# Schematic_v78.net
KiCad netlist of a schematic drawn in EAGLE
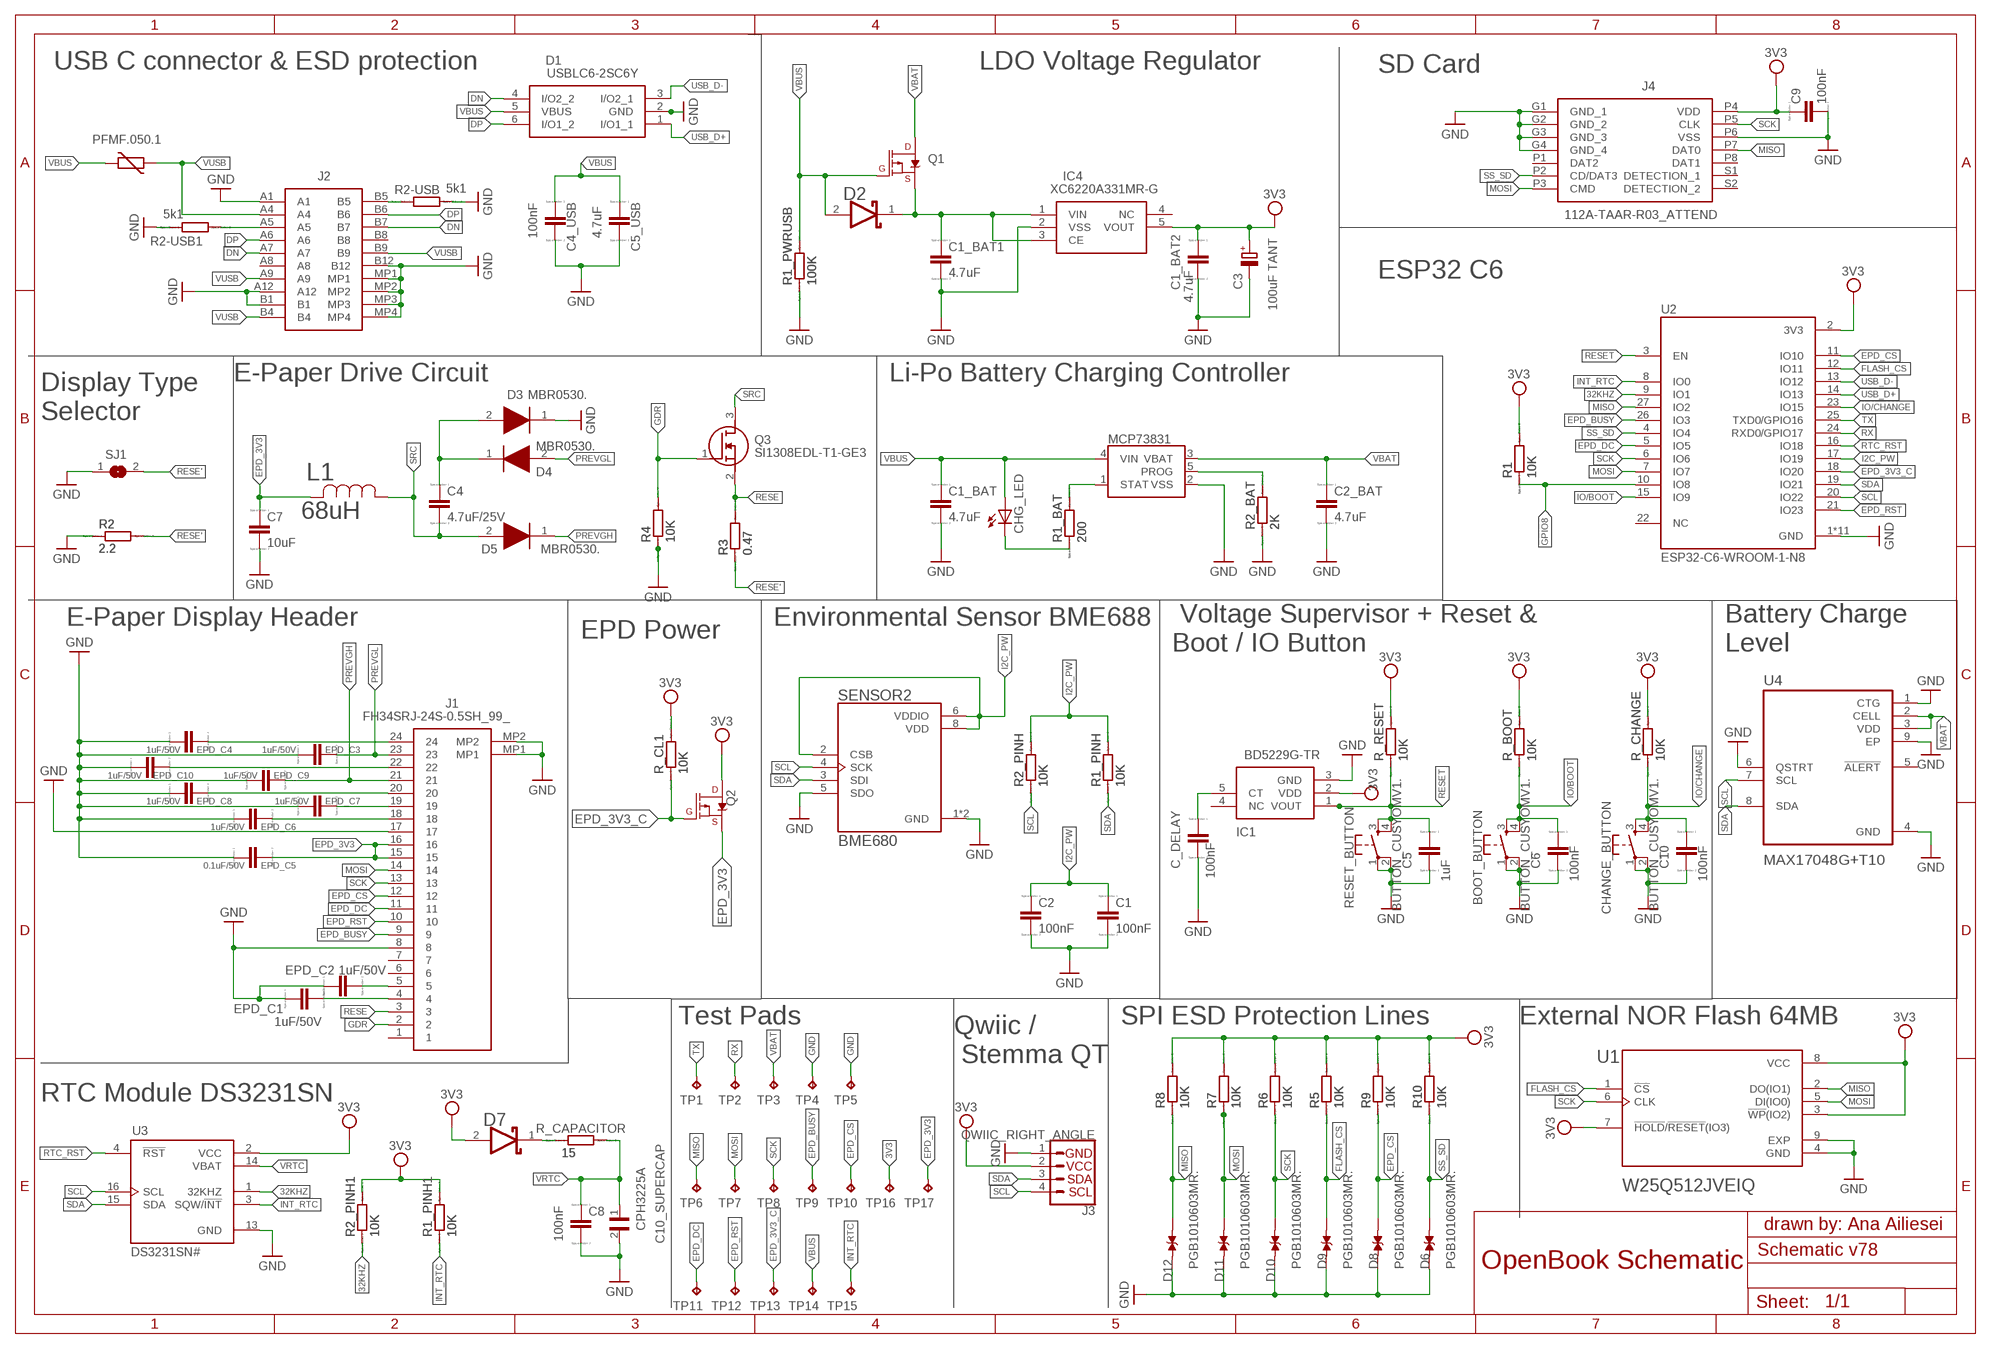
[diagram p0: schematic, sheet 1]

(export (version "E")
  (design (tool "Eeschema 10.0.6"))
  (components
    (comp (ref "BOOT_BUTTON")
      (value "BUTTON_CUSYOMV1.")
      (footprint "eagle-import:MYBUTTON")
      (libsource (lib "eagle-import") (part "BUTTON_CUSYOMV1."))
    )
    (comp (ref "C1")
      (value "100nF")
      (footprint "eagle-import:EAGLE-LTSPICE_C0402")
      (libsource (lib "eagle-import") (part "EAGLE-LTSPICE_C"))
    )
    (comp (ref "C1_BAT")
      (value "4.7uF")
      (footprint "eagle-import:EAGLE-LTSPICE_C0402")
      (libsource (lib "eagle-import") (part "EAGLE-LTSPICE_C"))
    )
    (comp (ref "C1_BAT1")
      (value "4.7uF")
      (footprint "eagle-import:EAGLE-LTSPICE_C0402")
      (libsource (lib "eagle-import") (part "EAGLE-LTSPICE_C"))
    )
    (comp (ref "C1_BAT2")
      (value "4.7uF")
      (footprint "eagle-import:EAGLE-LTSPICE_C0402")
      (libsource (lib "eagle-import") (part "EAGLE-LTSPICE_C"))
    )
    (comp (ref "C2")
      (value "100nF")
      (footprint "eagle-import:EAGLE-LTSPICE_C0402")
      (libsource (lib "eagle-import") (part "EAGLE-LTSPICE_C"))
    )
    (comp (ref "C2_BAT")
      (value "4.7uF")
      (footprint "eagle-import:EAGLE-LTSPICE_C0402")
      (libsource (lib "eagle-import") (part "EAGLE-LTSPICE_C"))
    )
    (comp (ref "C3")
      (value "100uF TANT")
      (footprint "eagle-import:RCL_CT3528")
      (libsource (lib "eagle-import") (part "RCL_CPOL-EUCT3528"))
    )
    (comp (ref "C4")
      (value "4.7uF/25V")
      (footprint "eagle-import:EAGLE-LTSPICE_C0402")
      (libsource (lib "eagle-import") (part "EAGLE-LTSPICE_C"))
    )
    (comp (ref "C4_USB")
      (value "100nF")
      (footprint "eagle-import:EAGLE-LTSPICE_C0402")
      (libsource (lib "eagle-import") (part "EAGLE-LTSPICE_C"))
    )
    (comp (ref "C5")
      (value "1uF")
      (footprint "eagle-import:EAGLE-LTSPICE_C0402")
      (libsource (lib "eagle-import") (part "EAGLE-LTSPICE_C"))
    )
    (comp (ref "C5_USB")
      (value "4.7uF")
      (footprint "eagle-import:EAGLE-LTSPICE_C0402")
      (libsource (lib "eagle-import") (part "EAGLE-LTSPICE_C"))
    )
    (comp (ref "C6")
      (value "100nF")
      (footprint "eagle-import:EAGLE-LTSPICE_C0402")
      (libsource (lib "eagle-import") (part "EAGLE-LTSPICE_C"))
    )
    (comp (ref "C7")
      (value "10uF")
      (footprint "eagle-import:EAGLE-LTSPICE_C0402")
      (libsource (lib "eagle-import") (part "EAGLE-LTSPICE_C"))
    )
    (comp (ref "C8")
      (value "100nF")
      (footprint "eagle-import:EAGLE-LTSPICE_C0402")
      (libsource (lib "eagle-import") (part "EAGLE-LTSPICE_C"))
    )
    (comp (ref "C9")
      (value "100nF")
      (footprint "eagle-import:EAGLE-LTSPICE_C0402")
      (libsource (lib "eagle-import") (part "EAGLE-LTSPICE_C"))
    )
    (comp (ref "C10")
      (value "100nF")
      (footprint "eagle-import:EAGLE-LTSPICE_C0402")
      (libsource (lib "eagle-import") (part "EAGLE-LTSPICE_C"))
    )
    (comp (ref "C10_SUPERCAP")
      (value "CPH3225A")
      (footprint "eagle-import:CAPCP3225X100N")
      (fields (field (name "MF") "Seiko Instruments"))
      (libsource (lib "eagle-import") (part "CPH3225A"))
    )
    (comp (ref "CHANGE_BUTTON")
      (value "BUTTON_CUSYOMV1.")
      (footprint "eagle-import:MYBUTTON")
      (libsource (lib "eagle-import") (part "BUTTON_CUSYOMV1."))
    )
    (comp (ref "CHG_LED")
      (value "ADAFRUIT_LEDCHIP-LED0603")
      (footprint "eagle-import:ADAFRUIT_CHIP-LED0603")
      (libsource (lib "eagle-import") (part "ADAFRUIT_LEDCHIP-LED0603"))
    )
    (comp (ref "C_DELAY")
      (value "100nF")
      (footprint "eagle-import:EAGLE-LTSPICE_C0402")
      (libsource (lib "eagle-import") (part "EAGLE-LTSPICE_C"))
    )
    (comp (ref "D1")
      (value "USBLC6-2SC6Y")
      (footprint "eagle-import:SOT95P280X145-6N")
      (fields (field (name "MF") "STMicroelectronics"))
      (libsource (lib "eagle-import") (part "USBLC6-2SC6Y"))
    )
    (comp (ref "D2")
      (value "ESP32_WROVER_AVX---SD0805S020S1R0_AVX_SD0805S020S1R0_0_0")
      (footprint "eagle-import:ESP32_WROVER_AVX---SD0805S020S1R0_AVX_SD0805S020S1R0_0")
      (libsource (lib "eagle-import") (part "ESP32_WROVER_AVX---SD0805S020S1R0_AVX_SD0805S020S1R0_0_0"))
    )
    (comp (ref "D3")
      (value "MBR0530.")
      (footprint "eagle-import:SOD3716X135N")
      (libsource (lib "eagle-import") (part "MBR0530."))
    )
    (comp (ref "D4")
      (value "MBR0530.")
      (footprint "eagle-import:SOD3716X135N")
      (libsource (lib "eagle-import") (part "MBR0530."))
    )
    (comp (ref "D5")
      (value "MBR0530.")
      (footprint "eagle-import:SOD3716X135N")
      (libsource (lib "eagle-import") (part "MBR0530."))
    )
    (comp (ref "D6")
      (value "PGB1010603MR.")
      (footprint "eagle-import:DIOC1608X36N")
      (libsource (lib "eagle-import") (part "PGB1010603MR."))
    )
    (comp (ref "D7")
      (value "SD0805S020S1R0")
      (footprint "eagle-import:ESP32_WROVER_AVX---SD0805S020S1R0_AVX_SD0805S020S1R0_0")
      (libsource (lib "eagle-import") (part "ESP32_WROVER_AVX---SD0805S020S1R0_AVX_SD0805S020S1R0_0_0"))
    )
    (comp (ref "D8")
      (value "PGB1010603MR.")
      (footprint "eagle-import:DIOC1608X36N")
      (libsource (lib "eagle-import") (part "PGB1010603MR."))
    )
    (comp (ref "D9")
      (value "PGB1010603MR.")
      (footprint "eagle-import:DIOC1608X36N")
      (libsource (lib "eagle-import") (part "PGB1010603MR."))
    )
    (comp (ref "D10")
      (value "PGB1010603MR.")
      (footprint "eagle-import:DIOC1608X36N")
      (libsource (lib "eagle-import") (part "PGB1010603MR."))
    )
    (comp (ref "D11")
      (value "PGB1010603MR.")
      (footprint "eagle-import:DIOC1608X36N")
      (libsource (lib "eagle-import") (part "PGB1010603MR."))
    )
    (comp (ref "D12")
      (value "PGB1010603MR.")
      (footprint "eagle-import:DIOC1608X36N")
      (libsource (lib "eagle-import") (part "PGB1010603MR."))
    )
    (comp (ref "EPD_C1")
      (value "1uF/50V")
      (footprint "eagle-import:EAGLE-LTSPICE_C0402")
      (libsource (lib "eagle-import") (part "EAGLE-LTSPICE_C"))
    )
    (comp (ref "EPD_C2")
      (value "1uF/50V")
      (footprint "eagle-import:EAGLE-LTSPICE_C0402")
      (libsource (lib "eagle-import") (part "EAGLE-LTSPICE_C"))
    )
    (comp (ref "EPD_C3")
      (value "1uF/50V")
      (footprint "eagle-import:EAGLE-LTSPICE_C0402")
      (libsource (lib "eagle-import") (part "EAGLE-LTSPICE_C"))
    )
    (comp (ref "EPD_C4")
      (value "1uF/50V")
      (footprint "eagle-import:EAGLE-LTSPICE_C0402")
      (libsource (lib "eagle-import") (part "EAGLE-LTSPICE_C"))
    )
    (comp (ref "EPD_C5")
      (value "0.1uF/50V")
      (footprint "eagle-import:EAGLE-LTSPICE_C0402")
      (libsource (lib "eagle-import") (part "EAGLE-LTSPICE_C"))
    )
    (comp (ref "EPD_C6")
      (value "1uF/50V")
      (footprint "eagle-import:EAGLE-LTSPICE_C0402")
      (libsource (lib "eagle-import") (part "EAGLE-LTSPICE_C"))
    )
    (comp (ref "EPD_C7")
      (value "1uF/50V")
      (footprint "eagle-import:EAGLE-LTSPICE_C0402")
      (libsource (lib "eagle-import") (part "EAGLE-LTSPICE_C"))
    )
    (comp (ref "EPD_C8")
      (value "1uF/50V")
      (footprint "eagle-import:EAGLE-LTSPICE_C0402")
      (libsource (lib "eagle-import") (part "EAGLE-LTSPICE_C"))
    )
    (comp (ref "EPD_C9")
      (value "1uF/50V")
      (footprint "eagle-import:EAGLE-LTSPICE_C0402")
      (libsource (lib "eagle-import") (part "EAGLE-LTSPICE_C"))
    )
    (comp (ref "EPD_C10")
      (value "1uF/50V")
      (footprint "eagle-import:EAGLE-LTSPICE_C0402")
      (libsource (lib "eagle-import") (part "EAGLE-LTSPICE_C"))
    )
    (comp (ref "IC1")
      (value "BD5229G-TR")
      (footprint "eagle-import:SOT95P280X125-5N")
      (fields (field (name "MOUSER_PART_NUMBER") "755-BD5229G-TR"))
      (libsource (lib "eagle-import") (part "BD5229G-TR"))
    )
    (comp (ref "IC4")
      (value "XC6220A331MR-G")
      (footprint "eagle-import:SOT95P280X120-5N")
      (fields (field (name "MOUSER_PART_NUMBER") "865-XC6220A331MR-G"))
      (libsource (lib "eagle-import") (part "XC6220A331MR-G"))
    )
    (comp (ref "J1")
      (value "FH34SRJ-24S-0.5SH_99_")
      (footprint "eagle-import:FH34SRJ24S05SH99")
      (fields
        (field (name "MANUFACTURER_PART_NUMBER") "FH34SRJ-24S-0.5SH(99)")
        (field (name "MOUSER_PART_NUMBER") "798-FH34SRJ24S05SH99")
      )
      (libsource (lib "eagle-import") (part "FH34SRJ-24S-0.5SH_99_"))
    )
    (comp (ref "J2")
      (value "SAMACSYS_PARTS_USB4110-GF-A")
      (footprint "eagle-import:SAMACSYS_PARTS_USB4110GFA")
      (fields
        (field (name "MANUFACTURER_PART_NUMBER") "USB4110-GF-A")
        (field (name "MOUSER_PART_NUMBER") "640-USB4110-GF-A")
      )
      (libsource (lib "eagle-import") (part "SAMACSYS_PARTS_USB4110-GF-A"))
    )
    (comp (ref "J3")
      (value "QWIIC_RIGHT_ANGLE")
      (footprint "eagle-import:JST04_1MM_RA")
      (libsource (lib "eagle-import") (part "QWIIC_CONNECTORJS-1MM"))
    )
    (comp (ref "J4")
      (value "112A-TAAR-R03_ATTEND")
      (footprint "eagle-import:112ATAARR03ATTEND")
      (fields (field (name "MANUFACTURER_PART_NUMBER") "112A-TAAR-R03 ATTEND"))
      (libsource (lib "eagle-import") (part "112A-TAAR-R03_ATTEND"))
    )
    (comp (ref "L1")
      (value "68uH")
      (footprint "eagle-import:IND_4828-WE-TPC_WRE")
      (fields
        (field (name "MANUFACTURER_PART_NUMBER") "744043680")
        (field (name "COPYRIGHT") "Copyright (C) 2024 Ultra Librarian. All rights reserved.")
      )
      (libsource (lib "eagle-import") (part "744043680IND_4828-WE-TPC_WRE"))
    )
    (comp (ref "MCP73831")
      (value "ESP32_WROVER_SPARKFUN-IC-POWER_MCP73831")
      (footprint "eagle-import:ESP32_WROVER_SPARKFUN-IC-POWER_SOT23-5")
      (libsource (lib "eagle-import") (part "ESP32_WROVER_SPARKFUN-IC-POWER_MCP73831"))
    )
    (comp (ref "PFMF.050.1")
      (value "ESP32C6_VARISTORCN1812")
      (footprint "eagle-import:ESP32C6_VARISTOR_CT_CN1812")
      (libsource (lib "eagle-import") (part "ESP32C6_VARISTORCN1812"))
    )
    (comp (ref "Q1")
      (value "20V/4.2A/52mΩ/1.4W")
      (footprint "eagle-import:ESP32_WROVER_SPARKFUN-DISCRETESEMI_SOT23-3")
      (libsource (lib "eagle-import") (part "ESP32_WROVER_SPARKFUN-DISCRETESEMI_MOSFET_PCH"))
    )
    (comp (ref "Q2")
      (value "20V/4.2A/52mΩ/1.4W")
      (footprint "eagle-import:ESP32_WROVER_SPARKFUN-DISCRETESEMI_SOT23-3")
      (libsource (lib "eagle-import") (part "ESP32_WROVER_SPARKFUN-DISCRETESEMI_MOSFET_PCH"))
    )
    (comp (ref "Q3")
      (value "SI1308EDL-T1-GE3")
      (footprint "eagle-import:SOT65P210X110-3N")
      (fields (field (name "MF") "Vishay Siliconix"))
      (libsource (lib "eagle-import") (part "SI1308EDL-T1-GE3"))
    )
    (comp (ref "R1")
      (value "10K")
      (footprint "eagle-import:ESP32_WROVER_EAGLE-LTSPICE_R0402")
      (libsource (lib "eagle-import") (part "ESP32_WROVER_EAGLE-LTSPICE_R"))
    )
    (comp (ref "R1_BAT")
      (value "200")
      (footprint "eagle-import:ESP32_WROVER_EAGLE-LTSPICE_R0402")
      (libsource (lib "eagle-import") (part "ESP32_WROVER_EAGLE-LTSPICE_R"))
    )
    (comp (ref "R1_PINH")
      (value "10K")
      (footprint "eagle-import:ESP32_WROVER_EAGLE-LTSPICE_R0402")
      (libsource (lib "eagle-import") (part "ESP32_WROVER_EAGLE-LTSPICE_R"))
    )
    (comp (ref "R1_PINH1")
      (value "10K")
      (footprint "eagle-import:ESP32_WROVER_EAGLE-LTSPICE_R0402")
      (libsource (lib "eagle-import") (part "ESP32_WROVER_EAGLE-LTSPICE_R"))
    )
    (comp (ref "R1_PWRUSB")
      (value "100K")
      (footprint "eagle-import:ESP32_WROVER_EAGLE-LTSPICE_R0402")
      (libsource (lib "eagle-import") (part "ESP32_WROVER_EAGLE-LTSPICE_R"))
    )
    (comp (ref "R2")
      (value "2.2")
      (footprint "eagle-import:ESP32_WROVER_EAGLE-LTSPICE_R0402")
      (libsource (lib "eagle-import") (part "ESP32_WROVER_EAGLE-LTSPICE_R"))
    )
    (comp (ref "R2-USB")
      (value "5k1")
      (footprint "eagle-import:ESP32_WROVER_EAGLE-LTSPICE_R0402")
      (libsource (lib "eagle-import") (part "ESP32_WROVER_EAGLE-LTSPICE_R"))
    )
    (comp (ref "R2-USB1")
      (value "5k1")
      (footprint "eagle-import:ESP32_WROVER_EAGLE-LTSPICE_R0402")
      (libsource (lib "eagle-import") (part "ESP32_WROVER_EAGLE-LTSPICE_R"))
    )
    (comp (ref "R2_BAT")
      (value "2K")
      (footprint "eagle-import:ESP32_WROVER_EAGLE-LTSPICE_R0402")
      (libsource (lib "eagle-import") (part "ESP32_WROVER_EAGLE-LTSPICE_R"))
    )
    (comp (ref "R2_PINH")
      (value "10K")
      (footprint "eagle-import:ESP32_WROVER_EAGLE-LTSPICE_R0402")
      (libsource (lib "eagle-import") (part "ESP32_WROVER_EAGLE-LTSPICE_R"))
    )
    (comp (ref "R2_PINH1")
      (value "10K")
      (footprint "eagle-import:ESP32_WROVER_EAGLE-LTSPICE_R0402")
      (libsource (lib "eagle-import") (part "ESP32_WROVER_EAGLE-LTSPICE_R"))
    )
    (comp (ref "R3")
      (value "0.47")
      (footprint "eagle-import:ESP32_WROVER_EAGLE-LTSPICE_R0402")
      (libsource (lib "eagle-import") (part "ESP32_WROVER_EAGLE-LTSPICE_R"))
    )
    (comp (ref "R4")
      (value "10K")
      (footprint "eagle-import:ESP32_WROVER_EAGLE-LTSPICE_R0402")
      (libsource (lib "eagle-import") (part "ESP32_WROVER_EAGLE-LTSPICE_R"))
    )
    (comp (ref "R5")
      (value "10K")
      (footprint "eagle-import:ESP32_WROVER_EAGLE-LTSPICE_R0402")
      (libsource (lib "eagle-import") (part "ESP32_WROVER_EAGLE-LTSPICE_R"))
    )
    (comp (ref "R6")
      (value "10K")
      (footprint "eagle-import:ESP32_WROVER_EAGLE-LTSPICE_R0402")
      (libsource (lib "eagle-import") (part "ESP32_WROVER_EAGLE-LTSPICE_R"))
    )
    (comp (ref "R7")
      (value "10K")
      (footprint "eagle-import:ESP32_WROVER_EAGLE-LTSPICE_R0402")
      (libsource (lib "eagle-import") (part "ESP32_WROVER_EAGLE-LTSPICE_R"))
    )
    (comp (ref "R8")
      (value "10K")
      (footprint "eagle-import:ESP32_WROVER_EAGLE-LTSPICE_R0402")
      (libsource (lib "eagle-import") (part "ESP32_WROVER_EAGLE-LTSPICE_R"))
    )
    (comp (ref "R9")
      (value "10K")
      (footprint "eagle-import:ESP32_WROVER_EAGLE-LTSPICE_R0402")
      (libsource (lib "eagle-import") (part "ESP32_WROVER_EAGLE-LTSPICE_R"))
    )
    (comp (ref "R10")
      (value "10K")
      (footprint "eagle-import:ESP32_WROVER_EAGLE-LTSPICE_R0402")
      (libsource (lib "eagle-import") (part "ESP32_WROVER_EAGLE-LTSPICE_R"))
    )
    (comp (ref "RESET_BUTTON")
      (value "BUTTON_CUSYOMV1.")
      (footprint "eagle-import:MYBUTTON")
      (libsource (lib "eagle-import") (part "BUTTON_CUSYOMV1."))
    )
    (comp (ref "R_BOOT")
      (value "10K")
      (footprint "eagle-import:ESP32_WROVER_EAGLE-LTSPICE_R0402")
      (libsource (lib "eagle-import") (part "ESP32_WROVER_EAGLE-LTSPICE_R"))
    )
    (comp (ref "R_CAPACITOR")
      (value "15")
      (footprint "eagle-import:ESP32_WROVER_EAGLE-LTSPICE_R0402")
      (libsource (lib "eagle-import") (part "ESP32_WROVER_EAGLE-LTSPICE_R"))
    )
    (comp (ref "R_CHANGE")
      (value "10K")
      (footprint "eagle-import:ESP32_WROVER_EAGLE-LTSPICE_R0402")
      (libsource (lib "eagle-import") (part "ESP32_WROVER_EAGLE-LTSPICE_R"))
    )
    (comp (ref "R_CL1")
      (value "10K")
      (footprint "eagle-import:ESP32_WROVER_EAGLE-LTSPICE_R0402")
      (libsource (lib "eagle-import") (part "ESP32_WROVER_EAGLE-LTSPICE_R"))
    )
    (comp (ref "R_RESET")
      (value "10K")
      (footprint "eagle-import:ESP32_WROVER_EAGLE-LTSPICE_R0402")
      (libsource (lib "eagle-import") (part "ESP32_WROVER_EAGLE-LTSPICE_R"))
    )
    (comp (ref "SENSOR2")
      (value "BME680")
      (footprint "eagle-import:ESP32_WROVER_BME680_PSON80P300X300X100-8N")
      (fields (field (name "MF") "Bosch Sensortec"))
      (libsource (lib "eagle-import") (part "ESP32_WROVER_BME680_BME680"))
    )
    (comp (ref "SJ1") (value "SJ") (footprint "eagle-import:SJ") (libsource (lib "eagle-import") (part "SJ")))
    (comp (ref "TP1")
      (value "TX")
      (footprint "eagle-import:TP20R")
      (libsource (lib "eagle-import") (part "TP"))
    )
    (comp (ref "TP2")
      (value "RX")
      (footprint "eagle-import:TP20R")
      (libsource (lib "eagle-import") (part "TP"))
    )
    (comp (ref "TP3")
      (value "VBAT")
      (footprint "eagle-import:TP20R")
      (libsource (lib "eagle-import") (part "TP"))
    )
    (comp (ref "TP4")
      (value "GND")
      (footprint "eagle-import:TP20R")
      (libsource (lib "eagle-import") (part "TP"))
    )
    (comp (ref "TP5")
      (value "GND")
      (footprint "eagle-import:TP20R")
      (libsource (lib "eagle-import") (part "TP"))
    )
    (comp (ref "TP6")
      (value "MISO")
      (footprint "eagle-import:TP20R")
      (libsource (lib "eagle-import") (part "TP"))
    )
    (comp (ref "TP7")
      (value "MOSI")
      (footprint "eagle-import:TP20R")
      (libsource (lib "eagle-import") (part "TP"))
    )
    (comp (ref "TP8")
      (value "SCK")
      (footprint "eagle-import:TP20R")
      (libsource (lib "eagle-import") (part "TP"))
    )
    (comp (ref "TP9")
      (value "EPD_BUSY")
      (footprint "eagle-import:TP20R")
      (libsource (lib "eagle-import") (part "TP"))
    )
    (comp (ref "TP10")
      (value "EPD_CS")
      (footprint "eagle-import:TP20R")
      (libsource (lib "eagle-import") (part "TP"))
    )
    (comp (ref "TP11")
      (value "EPD_DC")
      (footprint "eagle-import:TP20R")
      (libsource (lib "eagle-import") (part "TP"))
    )
    (comp (ref "TP12")
      (value "EPD_RST")
      (footprint "eagle-import:TP20R")
      (libsource (lib "eagle-import") (part "TP"))
    )
    (comp (ref "TP13")
      (value "EPD_3V3_C")
      (footprint "eagle-import:TP20R")
      (libsource (lib "eagle-import") (part "TP"))
    )
    (comp (ref "TP14")
      (value "VBUS")
      (footprint "eagle-import:TP20R")
      (libsource (lib "eagle-import") (part "TP"))
    )
    (comp (ref "TP15")
      (value "INT_RTC")
      (footprint "eagle-import:TP20R")
      (libsource (lib "eagle-import") (part "TP"))
    )
    (comp (ref "TP16")
      (value "3V3")
      (footprint "eagle-import:TP20R")
      (libsource (lib "eagle-import") (part "TP"))
    )
    (comp (ref "TP17")
      (value "EPD_3V3")
      (footprint "eagle-import:TP20R")
      (libsource (lib "eagle-import") (part "TP"))
    )
    (comp (ref "U1")
      (value "W25Q512JVEIQ")
      (footprint "eagle-import:SON127P600X800X80-9N")
      (fields (field (name "MF") "Winbond Electronics"))
      (libsource (lib "eagle-import") (part "W25Q512JVEIQ"))
    )
    (comp (ref "U2")
      (value "ESP32-C6-WROOM-1-N8")
      (footprint "eagle-import:XCVR_ESP32-C6-WROOM-1-N8")
      (fields (field (name "MF") "Espressif Systems"))
      (libsource (lib "eagle-import") (part "ESP32-C6-WROOM-1-N8"))
    )
    (comp (ref "U3")
      (value "DS3231SN#")
      (footprint "eagle-import:SOIC127P1032X265-16N")
      (fields (field (name "MF") "Analog Devices"))
      (libsource (lib "eagle-import") (part "DS3231SN#"))
    )
    (comp (ref "U4")
      (value "MAX17048G+T10")
      (footprint "eagle-import:SON50P200X200X80-9N")
      (fields (field (name "MF") "Analog Devices"))
      (libsource (lib "eagle-import") (part "MAX17048G+T10"))
    )
  )
  (nets
    (net (code "1") (name "3V3") (class "Default")
      (node (ref "C1_BAT2") (pin "1") (pinfunction "1_1") (pintype "passive"))
      (node (ref "C3") (pin "+") (pinfunction "+_+") (pintype "passive"))
      (node (ref "C9") (pin "1") (pinfunction "1_1") (pintype "passive"))
      (node (ref "D7") (pin "2") (pinfunction "ANODE_2") (pintype "bidirectional"))
      (node (ref "IC1") (pin "2") (pinfunction "VDD_2") (pintype "bidirectional"))
      (node (ref "IC4") (pin "5") (pinfunction "VOUT_5") (pintype "bidirectional"))
      (node (ref "J3") (pin "2") (pinfunction "2_2") (pintype "power_in"))
      (node (ref "J4") (pin "P4") (pinfunction "VDD_P4") (pintype "bidirectional"))
      (node (ref "Q2") (pin "3") (pinfunction "D_3") (pintype "bidirectional"))
      (node (ref "R1") (pin "2") (pinfunction "2_2") (pintype "passive"))
      (node (ref "R10") (pin "2") (pinfunction "2_2") (pintype "passive"))
      (node (ref "R1_PINH1") (pin "2") (pinfunction "2_2") (pintype "passive"))
      (node (ref "R2_PINH1") (pin "2") (pinfunction "2_2") (pintype "passive"))
      (node (ref "R5") (pin "2") (pinfunction "2_2") (pintype "passive"))
      (node (ref "R6") (pin "2") (pinfunction "2_2") (pintype "passive"))
      (node (ref "R7") (pin "2") (pinfunction "2_2") (pintype "passive"))
      (node (ref "R8") (pin "2") (pinfunction "2_2") (pintype "passive"))
      (node (ref "R9") (pin "2") (pinfunction "2_2") (pintype "passive"))
      (node (ref "R_BOOT") (pin "2") (pinfunction "2_2") (pintype "passive"))
      (node (ref "R_CHANGE") (pin "2") (pinfunction "2_2") (pintype "passive"))
      (node (ref "R_CL1") (pin "2") (pinfunction "2_2") (pintype "passive"))
      (node (ref "R_RESET") (pin "2") (pinfunction "2_2") (pintype "passive"))
      (node (ref "TP16") (pin "TP") (pinfunction "TP_TP") (pintype "input"))
      (node (ref "U1") (pin "3") (pinfunction "~{WP}(IO2)_3") (pintype "bidirectional"))
      (node (ref "U1") (pin "7") (pinfunction "~{HOLD}/~{RESET}(IO3)_7") (pintype "bidirectional"))
      (node (ref "U1") (pin "8") (pinfunction "VCC_8") (pintype "power_in"))
      (node (ref "U2") (pin "2") (pinfunction "3V3_2") (pintype "power_in"))
      (node (ref "U3") (pin "2") (pinfunction "VCC_2") (pintype "power_in"))
    )
    (net (code "2") (name "32KHZ") (class "Default")
      (node (ref "R2_PINH1") (pin "1") (pinfunction "1_1") (pintype "passive"))
      (node (ref "U2") (pin "9") (pinfunction "IO1_9") (pintype "bidirectional"))
      (node (ref "U3") (pin "1") (pinfunction "32KHZ_1") (pintype "output"))
    )
    (net (code "3") (name "DN") (class "Default")
      (node (ref "D1") (pin "4") (pinfunction "I/O2_2_4") (pintype "bidirectional"))
      (node (ref "J2") (pin "A7") (pinfunction "A7_A7") (pintype "bidirectional"))
      (node (ref "J2") (pin "B7") (pinfunction "B7_B7") (pintype "bidirectional"))
    )
    (net (code "4") (name "DP") (class "Default")
      (node (ref "D1") (pin "6") (pinfunction "I/O1_2_6") (pintype "bidirectional"))
      (node (ref "J2") (pin "A6") (pinfunction "A6_A6") (pintype "bidirectional"))
      (node (ref "J2") (pin "B6") (pinfunction "B6_B6") (pintype "bidirectional"))
    )
    (net (code "5") (name "EPD_3V3") (class "Default")
      (node (ref "C7") (pin "1") (pinfunction "1_1") (pintype "passive"))
      (node (ref "EPD_C5") (pin "2") (pinfunction "2_2") (pintype "passive"))
      (node (ref "J1") (pin "15") (pinfunction "15_15") (pintype "bidirectional"))
      (node (ref "J1") (pin "16") (pinfunction "16_16") (pintype "bidirectional"))
      (node (ref "L1") (pin "2") (pinfunction "2_2") (pintype "passive"))
      (node (ref "Q2") (pin "2") (pinfunction "S_2") (pintype "bidirectional"))
      (node (ref "TP17") (pin "TP") (pinfunction "TP_TP") (pintype "input"))
    )
    (net (code "6") (name "EPD_3V3_C") (class "Default")
      (node (ref "Q2") (pin "1") (pinfunction "G_1") (pintype "bidirectional"))
      (node (ref "R_CL1") (pin "1") (pinfunction "1_1") (pintype "passive"))
      (node (ref "TP13") (pin "TP") (pinfunction "TP_TP") (pintype "input"))
      (node (ref "U2") (pin "18") (pinfunction "IO20_18") (pintype "bidirectional"))
    )
    (net (code "7") (name "EPD_BUSY") (class "Default")
      (node (ref "J1") (pin "9") (pinfunction "9_9") (pintype "bidirectional"))
      (node (ref "TP9") (pin "TP") (pinfunction "TP_TP") (pintype "input"))
      (node (ref "U2") (pin "26") (pinfunction "IO3_26") (pintype "bidirectional"))
    )
    (net (code "8") (name "EPD_CS") (class "Default")
      (node (ref "D8") (pin "2") (pinfunction "2_2") (pintype "passive"))
      (node (ref "J1") (pin "12") (pinfunction "12_12") (pintype "bidirectional"))
      (node (ref "R9") (pin "1") (pinfunction "1_1") (pintype "passive"))
      (node (ref "TP10") (pin "TP") (pinfunction "TP_TP") (pintype "input"))
      (node (ref "U2") (pin "11") (pinfunction "IO10_11") (pintype "bidirectional"))
    )
    (net (code "9") (name "EPD_DC") (class "Default")
      (node (ref "J1") (pin "11") (pinfunction "11_11") (pintype "bidirectional"))
      (node (ref "TP11") (pin "TP") (pinfunction "TP_TP") (pintype "input"))
      (node (ref "U2") (pin "5") (pinfunction "IO5_5") (pintype "bidirectional"))
    )
    (net (code "10") (name "EPD_RST") (class "Default")
      (node (ref "J1") (pin "10") (pinfunction "10_10") (pintype "bidirectional"))
      (node (ref "TP12") (pin "TP") (pinfunction "TP_TP") (pintype "input"))
      (node (ref "U2") (pin "21") (pinfunction "IO23_21") (pintype "bidirectional"))
    )
    (net (code "11") (name "FLASH_CS") (class "Default")
      (node (ref "D9") (pin "2") (pinfunction "2_2") (pintype "passive"))
      (node (ref "R5") (pin "1") (pinfunction "1_1") (pintype "passive"))
      (node (ref "U1") (pin "1") (pinfunction "~{CS}_1") (pintype "input"))
      (node (ref "U2") (pin "12") (pinfunction "IO11_12") (pintype "bidirectional"))
    )
    (net (code "12") (name "GDR") (class "Default")
      (node (ref "J1") (pin "2") (pinfunction "2_2") (pintype "bidirectional"))
      (node (ref "Q3") (pin "1") (pinfunction "G_1") (pintype "bidirectional"))
      (node (ref "R4") (pin "2") (pinfunction "2_2") (pintype "passive"))
    )
    (net (code "13") (name "GND") (class "Default")
      (node (ref "BOOT_BUTTON") (pin "1") (pinfunction "1_1") (pintype "passive"))
      (node (ref "BOOT_BUTTON") (pin "2") (pinfunction "2_2") (pintype "passive"))
      (node (ref "C1") (pin "2") (pinfunction "2_2") (pintype "passive"))
      (node (ref "C10") (pin "2") (pinfunction "2_2") (pintype "passive"))
      (node (ref "C10_SUPERCAP") (pin "2") (pinfunction "2_2") (pintype "passive"))
      (node (ref "C1_BAT") (pin "2") (pinfunction "2_2") (pintype "passive"))
      (node (ref "C1_BAT1") (pin "2") (pinfunction "2_2") (pintype "passive"))
      (node (ref "C1_BAT2") (pin "2") (pinfunction "2_2") (pintype "passive"))
      (node (ref "C2") (pin "2") (pinfunction "2_2") (pintype "passive"))
      (node (ref "C2_BAT") (pin "2") (pinfunction "2_2") (pintype "passive"))
      (node (ref "C3") (pin "-") (pinfunction "-_-") (pintype "passive"))
      (node (ref "C4_USB") (pin "2") (pinfunction "2_2") (pintype "passive"))
      (node (ref "C5") (pin "2") (pinfunction "2_2") (pintype "passive"))
      (node (ref "C5_USB") (pin "2") (pinfunction "2_2") (pintype "passive"))
      (node (ref "C6") (pin "2") (pinfunction "2_2") (pintype "passive"))
      (node (ref "C7") (pin "2") (pinfunction "2_2") (pintype "passive"))
      (node (ref "C8") (pin "2") (pinfunction "2_2") (pintype "passive"))
      (node (ref "C9") (pin "2") (pinfunction "2_2") (pintype "passive"))
      (node (ref "CHANGE_BUTTON") (pin "1") (pinfunction "1_1") (pintype "passive"))
      (node (ref "CHANGE_BUTTON") (pin "2") (pinfunction "2_2") (pintype "passive"))
      (node (ref "C_DELAY") (pin "2") (pinfunction "2_2") (pintype "passive"))
      (node (ref "D1") (pin "2") (pinfunction "GND_2") (pintype "bidirectional"))
      (node (ref "D10") (pin "1") (pinfunction "1_1") (pintype "passive"))
      (node (ref "D11") (pin "1") (pinfunction "1_1") (pintype "passive"))
      (node (ref "D12") (pin "1") (pinfunction "1_1") (pintype "passive"))
      (node (ref "D3") (pin "1") (pinfunction "K_1") (pintype "bidirectional"))
      (node (ref "D6") (pin "1") (pinfunction "1_1") (pintype "passive"))
      (node (ref "D8") (pin "1") (pinfunction "1_1") (pintype "passive"))
      (node (ref "D9") (pin "1") (pinfunction "1_1") (pintype "passive"))
      (node (ref "EPD_C1") (pin "1") (pinfunction "1_1") (pintype "passive"))
      (node (ref "EPD_C10") (pin "1") (pinfunction "1_1") (pintype "passive"))
      (node (ref "EPD_C2") (pin "1") (pinfunction "1_1") (pintype "passive"))
      (node (ref "EPD_C3") (pin "1") (pinfunction "1_1") (pintype "passive"))
      (node (ref "EPD_C4") (pin "1") (pinfunction "1_1") (pintype "passive"))
      (node (ref "EPD_C5") (pin "1") (pinfunction "1_1") (pintype "passive"))
      (node (ref "EPD_C6") (pin "1") (pinfunction "1_1") (pintype "passive"))
      (node (ref "EPD_C7") (pin "1") (pinfunction "1_1") (pintype "passive"))
      (node (ref "EPD_C8") (pin "1") (pinfunction "1_1") (pintype "passive"))
      (node (ref "EPD_C9") (pin "1") (pinfunction "1_1") (pintype "passive"))
      (node (ref "IC1") (pin "3") (pinfunction "GND_3") (pintype "bidirectional"))
      (node (ref "IC4") (pin "2") (pinfunction "VSS_2") (pintype "bidirectional"))
      (node (ref "J1") (pin "17") (pinfunction "17_17") (pintype "bidirectional"))
      (node (ref "J1") (pin "8") (pinfunction "8_8") (pintype "bidirectional"))
      (node (ref "J1") (pin "MP1") (pinfunction "MP1_MP1") (pintype "bidirectional"))
      (node (ref "J1") (pin "MP2") (pinfunction "MP2_MP2") (pintype "bidirectional"))
      (node (ref "J2") (pin "A1") (pinfunction "A1_A1") (pintype "bidirectional"))
      (node (ref "J2") (pin "A12") (pinfunction "A12_A12") (pintype "bidirectional"))
      (node (ref "J2") (pin "B1") (pinfunction "B1_B1") (pintype "bidirectional"))
      (node (ref "J2") (pin "B12") (pinfunction "B12_B12") (pintype "bidirectional"))
      (node (ref "J2") (pin "MP1") (pinfunction "MP1_MP1") (pintype "bidirectional"))
      (node (ref "J2") (pin "MP2") (pinfunction "MP2_MP2") (pintype "bidirectional"))
      (node (ref "J2") (pin "MP3") (pinfunction "MP3_MP3") (pintype "bidirectional"))
      (node (ref "J2") (pin "MP4") (pinfunction "MP4_MP4") (pintype "bidirectional"))
      (node (ref "J3") (pin "1") (pinfunction "1_1") (pintype "power_in"))
      (node (ref "J4") (pin "G1") (pinfunction "GND_1_G1") (pintype "bidirectional"))
      (node (ref "J4") (pin "G2") (pinfunction "GND_2_G2") (pintype "bidirectional"))
      (node (ref "J4") (pin "G3") (pinfunction "GND_3_G3") (pintype "bidirectional"))
      (node (ref "J4") (pin "G4") (pinfunction "GND_4_G4") (pintype "bidirectional"))
      (node (ref "J4") (pin "P6") (pinfunction "VSS_P6") (pintype "bidirectional"))
      (node (ref "MCP73831") (pin "2") (pinfunction "VSS_2") (pintype "power_in"))
      (node (ref "R1_PWRUSB") (pin "1") (pinfunction "1_1") (pintype "passive"))
      (node (ref "R2") (pin "1") (pinfunction "1_1") (pintype "passive"))
      (node (ref "R2-USB") (pin "2") (pinfunction "2_2") (pintype "passive"))
      (node (ref "R2-USB1") (pin "1") (pinfunction "1_1") (pintype "passive"))
      (node (ref "R2_BAT") (pin "1") (pinfunction "1_1") (pintype "passive"))
      (node (ref "R4") (pin "1") (pinfunction "1_1") (pintype "passive"))
      (node (ref "RESET_BUTTON") (pin "1") (pinfunction "1_1") (pintype "passive"))
      (node (ref "RESET_BUTTON") (pin "2") (pinfunction "2_2") (pintype "passive"))
      (node (ref "SENSOR2") (pin "1") (pinfunction "GND_1") (pintype "power_in"))
      (node (ref "SENSOR2") (pin "5") (pinfunction "SDO_5") (pintype "bidirectional"))
      (node (ref "SENSOR2") (pin "7") (pinfunction "GND_7") (pintype "power_in"))
      (node (ref "SJ1") (pin "1") (pinfunction "1_1") (pintype "passive"))
      (node (ref "TP4") (pin "TP") (pinfunction "TP_TP") (pintype "input"))
      (node (ref "TP5") (pin "TP") (pinfunction "TP_TP") (pintype "input"))
      (node (ref "U1") (pin "4") (pinfunction "GND_4") (pintype "power_in"))
      (node (ref "U1") (pin "9") (pinfunction "EXP_9") (pintype "passive"))
      (node (ref "U2") (pin "1") (pinfunction "GND_1") (pintype "power_in"))
      (node (ref "U2") (pin "28") (pinfunction "GND_28") (pintype "power_in"))
      (node (ref "U2") (pin "29_1") (pinfunction "GND_29_1") (pintype "power_in"))
      (node (ref "U2") (pin "29_2") (pinfunction "GND_29_2") (pintype "power_in"))
      (node (ref "U2") (pin "29_3") (pinfunction "GND_29_3") (pintype "power_in"))
      (node (ref "U2") (pin "29_4") (pinfunction "GND_29_4") (pintype "power_in"))
      (node (ref "U2") (pin "29_5") (pinfunction "GND_29_5") (pintype "power_in"))
      (node (ref "U2") (pin "29_6") (pinfunction "GND_29_6") (pintype "power_in"))
      (node (ref "U2") (pin "29_7") (pinfunction "GND_29_7") (pintype "power_in"))
      (node (ref "U2") (pin "29_8") (pinfunction "GND_29_8") (pintype "power_in"))
      (node (ref "U2") (pin "29_9") (pinfunction "GND_29_9") (pintype "power_in"))
      (node (ref "U3") (pin "13") (pinfunction "GND_13") (pintype "power_in"))
      (node (ref "U4") (pin "1") (pinfunction "CTG_1") (pintype "power_in"))
      (node (ref "U4") (pin "4") (pinfunction "GND_4") (pintype "power_in"))
      (node (ref "U4") (pin "6") (pinfunction "QSTRT_6") (pintype "input"))
      (node (ref "U4") (pin "9") (pinfunction "EP_9") (pintype "power_in"))
    )
    (net (code "14") (name "GPIO8") (class "Default")
      (node (ref "R1") (pin "1") (pinfunction "1_1") (pintype "passive"))
      (node (ref "U2") (pin "10") (pinfunction "IO8_10") (pintype "bidirectional"))
    )
    (net (code "15") (name "I2C_PW") (class "Default")
      (node (ref "C1") (pin "1") (pinfunction "1_1") (pintype "passive"))
      (node (ref "C2") (pin "1") (pinfunction "1_1") (pintype "passive"))
      (node (ref "R1_PINH") (pin "2") (pinfunction "2_2") (pintype "passive"))
      (node (ref "R2_PINH") (pin "2") (pinfunction "2_2") (pintype "passive"))
      (node (ref "SENSOR2") (pin "2") (pinfunction "CSB_2") (pintype "input"))
      (node (ref "SENSOR2") (pin "6") (pinfunction "VDDIO_6") (pintype "power_in"))
      (node (ref "SENSOR2") (pin "8") (pinfunction "VDD_8") (pintype "power_in"))
      (node (ref "U2") (pin "17") (pinfunction "IO19_17") (pintype "bidirectional"))
    )
    (net (code "16") (name "INT_RTC") (class "Default")
      (node (ref "R1_PINH1") (pin "1") (pinfunction "1_1") (pintype "passive"))
      (node (ref "TP15") (pin "TP") (pinfunction "TP_TP") (pintype "input"))
      (node (ref "U2") (pin "8") (pinfunction "IO0_8") (pintype "bidirectional"))
      (node (ref "U3") (pin "3") (pinfunction "SQW/~{INT}_3") (pintype "output"))
    )
    (net (code "17") (name "IO{slash}BOOT") (class "Default")
      (node (ref "BOOT_BUTTON") (pin "3") (pinfunction "3_3") (pintype "passive"))
      (node (ref "BOOT_BUTTON") (pin "4") (pinfunction "4_4") (pintype "passive"))
      (node (ref "C6") (pin "1") (pinfunction "1_1") (pintype "passive"))
      (node (ref "R_BOOT") (pin "1") (pinfunction "1_1") (pintype "passive"))
      (node (ref "U2") (pin "15") (pinfunction "IO9_15") (pintype "bidirectional"))
    )
    (net (code "18") (name "IO{slash}CHANGE") (class "Default")
      (node (ref "C10") (pin "1") (pinfunction "1_1") (pintype "passive"))
      (node (ref "CHANGE_BUTTON") (pin "3") (pinfunction "3_3") (pintype "passive"))
      (node (ref "CHANGE_BUTTON") (pin "4") (pinfunction "4_4") (pintype "passive"))
      (node (ref "R_CHANGE") (pin "1") (pinfunction "1_1") (pintype "passive"))
      (node (ref "U2") (pin "23") (pinfunction "IO15_23") (pintype "bidirectional"))
    )
    (net (code "19") (name "MISO") (class "Default")
      (node (ref "D12") (pin "2") (pinfunction "2_2") (pintype "passive"))
      (node (ref "J4") (pin "P7") (pinfunction "DAT0_P7") (pintype "bidirectional"))
      (node (ref "R8") (pin "1") (pinfunction "1_1") (pintype "passive"))
      (node (ref "TP6") (pin "TP") (pinfunction "TP_TP") (pintype "input"))
      (node (ref "U1") (pin "2") (pinfunction "DO(IO1)_2") (pintype "bidirectional"))
      (node (ref "U2") (pin "27") (pinfunction "IO2_27") (pintype "bidirectional"))
    )
    (net (code "20") (name "MOSI") (class "Default")
      (node (ref "D11") (pin "2") (pinfunction "2_2") (pintype "passive"))
      (node (ref "J1") (pin "14") (pinfunction "14_14") (pintype "bidirectional"))
      (node (ref "J4") (pin "P3") (pinfunction "CMD_P3") (pintype "bidirectional"))
      (node (ref "R7") (pin "1") (pinfunction "1_1") (pintype "passive"))
      (node (ref "TP7") (pin "TP") (pinfunction "TP_TP") (pintype "input"))
      (node (ref "U1") (pin "5") (pinfunction "DI(IO0)_5") (pintype "bidirectional"))
      (node (ref "U2") (pin "7") (pinfunction "IO7_7") (pintype "bidirectional"))
    )
    (net (code "21") (name "Net-(CHG_LED-PadC)") (class "Default")
      (node (ref "CHG_LED") (pin "C") (pinfunction "C_C") (pintype "passive"))
      (node (ref "R1_BAT") (pin "1") (pinfunction "1_1") (pintype "passive"))
    )
    (net (code "22") (name "Net-(D2-CATHODE)") (class "Default")
      (node (ref "C1_BAT1") (pin "1") (pinfunction "1_1") (pintype "passive"))
      (node (ref "D2") (pin "1") (pinfunction "CATHODE_1") (pintype "bidirectional"))
      (node (ref "IC4") (pin "1") (pinfunction "VIN_1") (pintype "bidirectional"))
      (node (ref "IC4") (pin "3") (pinfunction "CE_3") (pintype "bidirectional"))
      (node (ref "Q1") (pin "2") (pinfunction "S_2") (pintype "bidirectional"))
    )
    (net (code "23") (name "Net-(D3-A)") (class "Default")
      (node (ref "C4") (pin "1") (pinfunction "1_1") (pintype "passive"))
      (node (ref "D3") (pin "2") (pinfunction "A_2") (pintype "bidirectional"))
      (node (ref "D4") (pin "1") (pinfunction "K_1") (pintype "bidirectional"))
    )
    (net (code "24") (name "Net-(D7-CATHODE)") (class "Default")
      (node (ref "D7") (pin "1") (pinfunction "CATHODE_1") (pintype "bidirectional"))
      (node (ref "R_CAPACITOR") (pin "1") (pinfunction "1_1") (pintype "passive"))
    )
    (net (code "25") (name "Net-(EPD_C1-Pad2)") (class "Default")
      (node (ref "EPD_C1") (pin "2") (pinfunction "2_2") (pintype "passive"))
      (node (ref "J1") (pin "4") (pinfunction "4_4") (pintype "bidirectional"))
    )
    (net (code "26") (name "Net-(EPD_C2-Pad2)") (class "Default")
      (node (ref "EPD_C2") (pin "2") (pinfunction "2_2") (pintype "passive"))
      (node (ref "J1") (pin "5") (pinfunction "5_5") (pintype "bidirectional"))
    )
    (net (code "27") (name "Net-(EPD_C4-Pad2)") (class "Default")
      (node (ref "EPD_C4") (pin "2") (pinfunction "2_2") (pintype "passive"))
      (node (ref "J1") (pin "24") (pinfunction "24_24") (pintype "bidirectional"))
    )
    (net (code "28") (name "Net-(EPD_C6-Pad2)") (class "Default")
      (node (ref "EPD_C6") (pin "2") (pinfunction "2_2") (pintype "passive"))
      (node (ref "J1") (pin "18") (pinfunction "18_18") (pintype "bidirectional"))
    )
    (net (code "29") (name "Net-(EPD_C7-Pad2)") (class "Default")
      (node (ref "EPD_C7") (pin "2") (pinfunction "2_2") (pintype "passive"))
      (node (ref "J1") (pin "19") (pinfunction "19_19") (pintype "bidirectional"))
    )
    (net (code "30") (name "Net-(EPD_C8-Pad2)") (class "Default")
      (node (ref "EPD_C8") (pin "2") (pinfunction "2_2") (pintype "passive"))
      (node (ref "J1") (pin "20") (pinfunction "20_20") (pintype "bidirectional"))
    )
    (net (code "31") (name "Net-(EPD_C10-Pad2)") (class "Default")
      (node (ref "EPD_C10") (pin "2") (pinfunction "2_2") (pintype "passive"))
      (node (ref "J1") (pin "22") (pinfunction "22_22") (pintype "bidirectional"))
    )
    (net (code "32") (name "Net-(IC1-CT)") (class "Default")
      (node (ref "C_DELAY") (pin "1") (pinfunction "1_1") (pintype "passive"))
      (node (ref "IC1") (pin "5") (pinfunction "CT_5") (pintype "bidirectional"))
    )
    (net (code "33") (name "Net-(J2-PadA5)") (class "Default")
      (node (ref "J2") (pin "A5") (pinfunction "A5_A5") (pintype "bidirectional"))
      (node (ref "R2-USB1") (pin "2") (pinfunction "2_2") (pintype "passive"))
    )
    (net (code "34") (name "Net-(J2-PadB5)") (class "Default")
      (node (ref "J2") (pin "B5") (pinfunction "B5_B5") (pintype "bidirectional"))
      (node (ref "R2-USB") (pin "1") (pinfunction "1_1") (pintype "passive"))
    )
    (net (code "35") (name "Net-(MCP73831-PROG)") (class "Default")
      (node (ref "MCP73831") (pin "5") (pinfunction "PROG_5") (pintype "input"))
      (node (ref "R2_BAT") (pin "2") (pinfunction "2_2") (pintype "passive"))
    )
    (net (code "36") (name "Net-(MCP73831-STAT)") (class "Default")
      (node (ref "MCP73831") (pin "1") (pinfunction "STAT_1") (pintype "output"))
      (node (ref "R1_BAT") (pin "2") (pinfunction "2_2") (pintype "passive"))
    )
    (net (code "37") (name "PREVGH") (class "Default")
      (node (ref "D5") (pin "1") (pinfunction "K_1") (pintype "bidirectional"))
      (node (ref "EPD_C9") (pin "2") (pinfunction "2_2") (pintype "passive"))
      (node (ref "J1") (pin "21") (pinfunction "21_21") (pintype "bidirectional"))
    )
    (net (code "38") (name "PREVGL") (class "Default")
      (node (ref "D4") (pin "2") (pinfunction "A_2") (pintype "bidirectional"))
      (node (ref "EPD_C3") (pin "2") (pinfunction "2_2") (pintype "passive"))
      (node (ref "J1") (pin "23") (pinfunction "23_23") (pintype "bidirectional"))
    )
    (net (code "39") (name "RESE") (class "Default")
      (node (ref "J1") (pin "3") (pinfunction "3_3") (pintype "bidirectional"))
      (node (ref "Q3") (pin "2") (pinfunction "S_2") (pintype "bidirectional"))
      (node (ref "R3") (pin "2") (pinfunction "2_2") (pintype "passive"))
    )
    (net (code "40") (name "RESE'") (class "Default")
      (node (ref "R2") (pin "2") (pinfunction "2_2") (pintype "passive"))
      (node (ref "R3") (pin "1") (pinfunction "1_1") (pintype "passive"))
      (node (ref "SJ1") (pin "2") (pinfunction "2_2") (pintype "passive"))
    )
    (net (code "41") (name "RESET") (class "Default")
      (node (ref "C5") (pin "1") (pinfunction "1_1") (pintype "passive"))
      (node (ref "IC1") (pin "1") (pinfunction "VOUT_1") (pintype "bidirectional"))
      (node (ref "RESET_BUTTON") (pin "3") (pinfunction "3_3") (pintype "passive"))
      (node (ref "RESET_BUTTON") (pin "4") (pinfunction "4_4") (pintype "passive"))
      (node (ref "R_RESET") (pin "1") (pinfunction "1_1") (pintype "passive"))
      (node (ref "U2") (pin "3") (pinfunction "EN_3") (pintype "input"))
    )
    (net (code "42") (name "RTC_RST") (class "Default")
      (node (ref "U2") (pin "16") (pinfunction "IO18_16") (pintype "bidirectional"))
      (node (ref "U3") (pin "4") (pinfunction "~{RST}_4") (pintype "input"))
    )
    (net (code "43") (name "RX") (class "Default")
      (node (ref "TP2") (pin "TP") (pinfunction "TP_TP") (pintype "input"))
      (node (ref "U2") (pin "24") (pinfunction "RXD0/GPIO17_24") (pintype "bidirectional"))
    )
    (net (code "44") (name "SCK") (class "Default")
      (node (ref "D10") (pin "2") (pinfunction "2_2") (pintype "passive"))
      (node (ref "J1") (pin "13") (pinfunction "13_13") (pintype "bidirectional"))
      (node (ref "J4") (pin "P5") (pinfunction "CLK_P5") (pintype "bidirectional"))
      (node (ref "R6") (pin "1") (pinfunction "1_1") (pintype "passive"))
      (node (ref "TP8") (pin "TP") (pinfunction "TP_TP") (pintype "input"))
      (node (ref "U1") (pin "6") (pinfunction "CLK_6") (pintype "input"))
      (node (ref "U2") (pin "6") (pinfunction "IO6_6") (pintype "bidirectional"))
    )
    (net (code "45") (name "SCL") (class "Default")
      (node (ref "J3") (pin "4") (pinfunction "4_4") (pintype "passive"))
      (node (ref "R2_PINH") (pin "1") (pinfunction "1_1") (pintype "passive"))
      (node (ref "SENSOR2") (pin "4") (pinfunction "SCK_4") (pintype "input"))
      (node (ref "U2") (pin "20") (pinfunction "IO22_20") (pintype "bidirectional"))
      (node (ref "U3") (pin "16") (pinfunction "SCL_16") (pintype "input"))
      (node (ref "U4") (pin "7") (pinfunction "SCL_7") (pintype "input"))
    )
    (net (code "46") (name "SDA") (class "Default")
      (node (ref "J3") (pin "3") (pinfunction "3_3") (pintype "passive"))
      (node (ref "R1_PINH") (pin "1") (pinfunction "1_1") (pintype "passive"))
      (node (ref "SENSOR2") (pin "3") (pinfunction "SDI_3") (pintype "bidirectional"))
      (node (ref "U2") (pin "19") (pinfunction "IO21_19") (pintype "bidirectional"))
      (node (ref "U3") (pin "15") (pinfunction "SDA_15") (pintype "bidirectional"))
      (node (ref "U4") (pin "8") (pinfunction "SDA_8") (pintype "bidirectional"))
    )
    (net (code "47") (name "SRC") (class "Default")
      (node (ref "C4") (pin "2") (pinfunction "2_2") (pintype "passive"))
      (node (ref "D5") (pin "2") (pinfunction "A_2") (pintype "bidirectional"))
      (node (ref "L1") (pin "1") (pinfunction "1_1") (pintype "passive"))
      (node (ref "Q3") (pin "3") (pinfunction "D_3") (pintype "bidirectional"))
    )
    (net (code "48") (name "SS_SD") (class "Default")
      (node (ref "D6") (pin "2") (pinfunction "2_2") (pintype "passive"))
      (node (ref "J4") (pin "P2") (pinfunction "CD/DAT3_P2") (pintype "bidirectional"))
      (node (ref "R10") (pin "1") (pinfunction "1_1") (pintype "passive"))
      (node (ref "U2") (pin "4") (pinfunction "IO4_4") (pintype "bidirectional"))
    )
    (net (code "49") (name "TX") (class "Default")
      (node (ref "TP1") (pin "TP") (pinfunction "TP_TP") (pintype "input"))
      (node (ref "U2") (pin "25") (pinfunction "TXD0/GPIO16_25") (pintype "bidirectional"))
    )
    (net (code "50") (name "USB_D+") (class "Default")
      (node (ref "D1") (pin "1") (pinfunction "I/O1_1_1") (pintype "bidirectional"))
      (node (ref "U2") (pin "14") (pinfunction "IO13_14") (pintype "bidirectional"))
    )
    (net (code "51") (name "USB_D-") (class "Default")
      (node (ref "D1") (pin "3") (pinfunction "I/O2_1_3") (pintype "bidirectional"))
      (node (ref "U2") (pin "13") (pinfunction "IO12_13") (pintype "bidirectional"))
    )
    (net (code "52") (name "VBAT") (class "Default")
      (node (ref "C2_BAT") (pin "1") (pinfunction "1_1") (pintype "passive"))
      (node (ref "MCP73831") (pin "3") (pinfunction "VBAT_3") (pintype "power_in"))
      (node (ref "Q1") (pin "3") (pinfunction "D_3") (pintype "bidirectional"))
      (node (ref "TP3") (pin "TP") (pinfunction "TP_TP") (pintype "input"))
      (node (ref "U4") (pin "2") (pinfunction "CELL_2") (pintype "power_in"))
      (node (ref "U4") (pin "3") (pinfunction "VDD_3") (pintype "power_in"))
    )
    (net (code "53") (name "VBUS") (class "Default")
      (node (ref "C1_BAT") (pin "1") (pinfunction "1_1") (pintype "passive"))
      (node (ref "C4_USB") (pin "1") (pinfunction "1_1") (pintype "passive"))
      (node (ref "C5_USB") (pin "1") (pinfunction "1_1") (pintype "passive"))
      (node (ref "CHG_LED") (pin "A") (pinfunction "A_A") (pintype "passive"))
      (node (ref "D1") (pin "5") (pinfunction "VBUS_5") (pintype "bidirectional"))
      (node (ref "D2") (pin "2") (pinfunction "ANODE_2") (pintype "bidirectional"))
      (node (ref "MCP73831") (pin "4") (pinfunction "VIN_4") (pintype "power_in"))
      (node (ref "PFMF.050.1") (pin "2") (pinfunction "2_2") (pintype "passive"))
      (node (ref "Q1") (pin "1") (pinfunction "G_1") (pintype "bidirectional"))
      (node (ref "R1_PWRUSB") (pin "2") (pinfunction "2_2") (pintype "passive"))
      (node (ref "TP14") (pin "TP") (pinfunction "TP_TP") (pintype "input"))
    )
    (net (code "54") (name "VRTC") (class "Default")
      (node (ref "C10_SUPERCAP") (pin "1") (pinfunction "1_1") (pintype "passive"))
      (node (ref "C8") (pin "1") (pinfunction "1_1") (pintype "passive"))
      (node (ref "R_CAPACITOR") (pin "2") (pinfunction "2_2") (pintype "passive"))
      (node (ref "U3") (pin "14") (pinfunction "VBAT_14") (pintype "power_in"))
    )
    (net (code "55") (name "VUSB") (class "Default")
      (node (ref "J2") (pin "A4") (pinfunction "A4_A4") (pintype "bidirectional"))
      (node (ref "J2") (pin "A9") (pinfunction "A9_A9") (pintype "bidirectional"))
      (node (ref "J2") (pin "B4") (pinfunction "B4_B4") (pintype "bidirectional"))
      (node (ref "J2") (pin "B9") (pinfunction "B9_B9") (pintype "bidirectional"))
      (node (ref "PFMF.050.1") (pin "1") (pinfunction "1_1") (pintype "passive"))
    )
    (net (code "56") (name "unconnected-(IC1-NC-Pad4)") (class "Default")
      (node (ref "IC1") (pin "4") (pinfunction "NC_4") (pintype "no_connect"))
    )
    (net (code "57") (name "unconnected-(IC4-NC-Pad4)") (class "Default")
      (node (ref "IC4") (pin "4") (pinfunction "NC_4") (pintype "no_connect"))
    )
    (net (code "58") (name "unconnected-(J1-Pad1)") (class "Default")
      (node (ref "J1") (pin "1") (pinfunction "1_1") (pintype "bidirectional"))
    )
    (net (code "59") (name "unconnected-(J1-Pad6)") (class "Default")
      (node (ref "J1") (pin "6") (pinfunction "6_6") (pintype "bidirectional"))
    )
    (net (code "60") (name "unconnected-(J1-Pad7)") (class "Default")
      (node (ref "J1") (pin "7") (pinfunction "7_7") (pintype "bidirectional"))
    )
    (net (code "61") (name "unconnected-(J2-PadA8)") (class "Default")
      (node (ref "J2") (pin "A8") (pinfunction "A8_A8") (pintype "bidirectional"))
    )
    (net (code "62") (name "unconnected-(J2-PadB8)") (class "Default")
      (node (ref "J2") (pin "B8") (pinfunction "B8_B8") (pintype "bidirectional"))
    )
    (net (code "63") (name "unconnected-(J4-DAT1-PadP8)") (class "Default")
      (node (ref "J4") (pin "P8") (pinfunction "DAT1_P8") (pintype "bidirectional"))
    )
    (net (code "64") (name "unconnected-(J4-DAT2-PadP1)") (class "Default")
      (node (ref "J4") (pin "P1") (pinfunction "DAT2_P1") (pintype "bidirectional"))
    )
    (net (code "65") (name "unconnected-(J4-DETECTION_1-PadS1)") (class "Default")
      (node (ref "J4") (pin "S1") (pinfunction "DETECTION_1_S1") (pintype "bidirectional"))
    )
    (net (code "66") (name "unconnected-(J4-DETECTION_2-PadS2)") (class "Default")
      (node (ref "J4") (pin "S2") (pinfunction "DETECTION_2_S2") (pintype "bidirectional"))
    )
    (net (code "67") (name "unconnected-(U2-NC-Pad22)") (class "Default")
      (node (ref "U2") (pin "22") (pinfunction "NC_22") (pintype "no_connect"))
    )
    (net (code "68") (name "unconnected-(U4-~{ALERT}-Pad5)") (class "Default")
      (node (ref "U4") (pin "5") (pinfunction "~{ALERT}_5") (pintype "output"))
    )
  )
)
